# Sheet1.net
KiCad netlist of a schematic drawn in Altium Designer
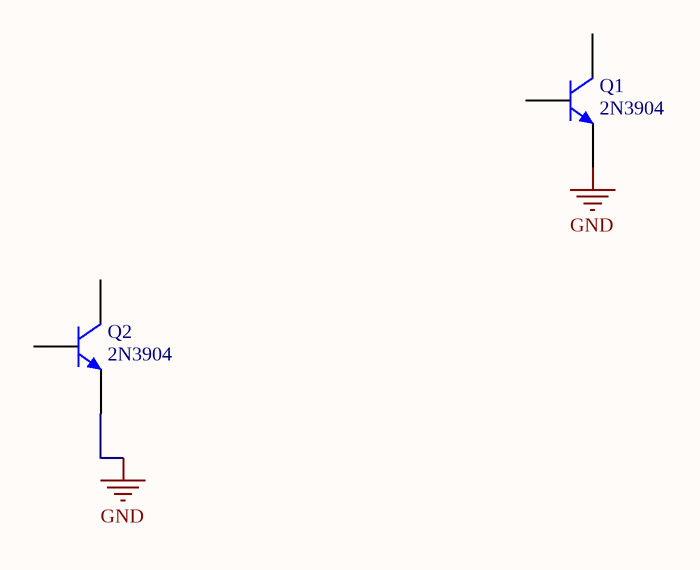
[diagram p0: Sheet1.SchDoc]

(export (version "E")
  (design (tool "Eeschema 10.0.6"))
  (components
    (comp (ref "Q1")
      (value "2N3904")
      (footprint "TO-92A")
      (description "NPN General Purpose Amplifier")
      (fields (field (name "PUBLISHER") "Altium Limited"))
      (libsource (lib "Miscellaneous Devices") (part "2N3904"))
    )
    (comp (ref "Q2")
      (value "2N3904")
      (footprint "TO-92A")
      (description "NPN General Purpose Amplifier")
      (fields (field (name "PUBLISHER") "Altium Limited"))
      (libsource (lib "Miscellaneous Devices") (part "2N3904"))
    )
  )
  (nets
    (net (code "1") (name "GND") (class "Default")
      (node (ref "Q1") (pin "1") (pinfunction "E_1") (pintype "passive"))
      (node (ref "Q2") (pin "1") (pinfunction "E_1") (pintype "passive"))
    )
    (net (code "2") (name "unconnected-(Q1-B-Pad2)") (class "Default")
      (node (ref "Q1") (pin "2") (pinfunction "B_2") (pintype "passive"))
    )
    (net (code "3") (name "unconnected-(Q1-C-Pad3)") (class "Default")
      (node (ref "Q1") (pin "3") (pinfunction "C_3") (pintype "passive"))
    )
    (net (code "4") (name "unconnected-(Q2-B-Pad2)") (class "Default")
      (node (ref "Q2") (pin "2") (pinfunction "B_2") (pintype "passive"))
    )
    (net (code "5") (name "unconnected-(Q2-C-Pad3)") (class "Default")
      (node (ref "Q2") (pin "3") (pinfunction "C_3") (pintype "passive"))
    )
  )
)
